# UWB-Tag_Sch.net
KiCad netlist of a schematic drawn in Altium Designer
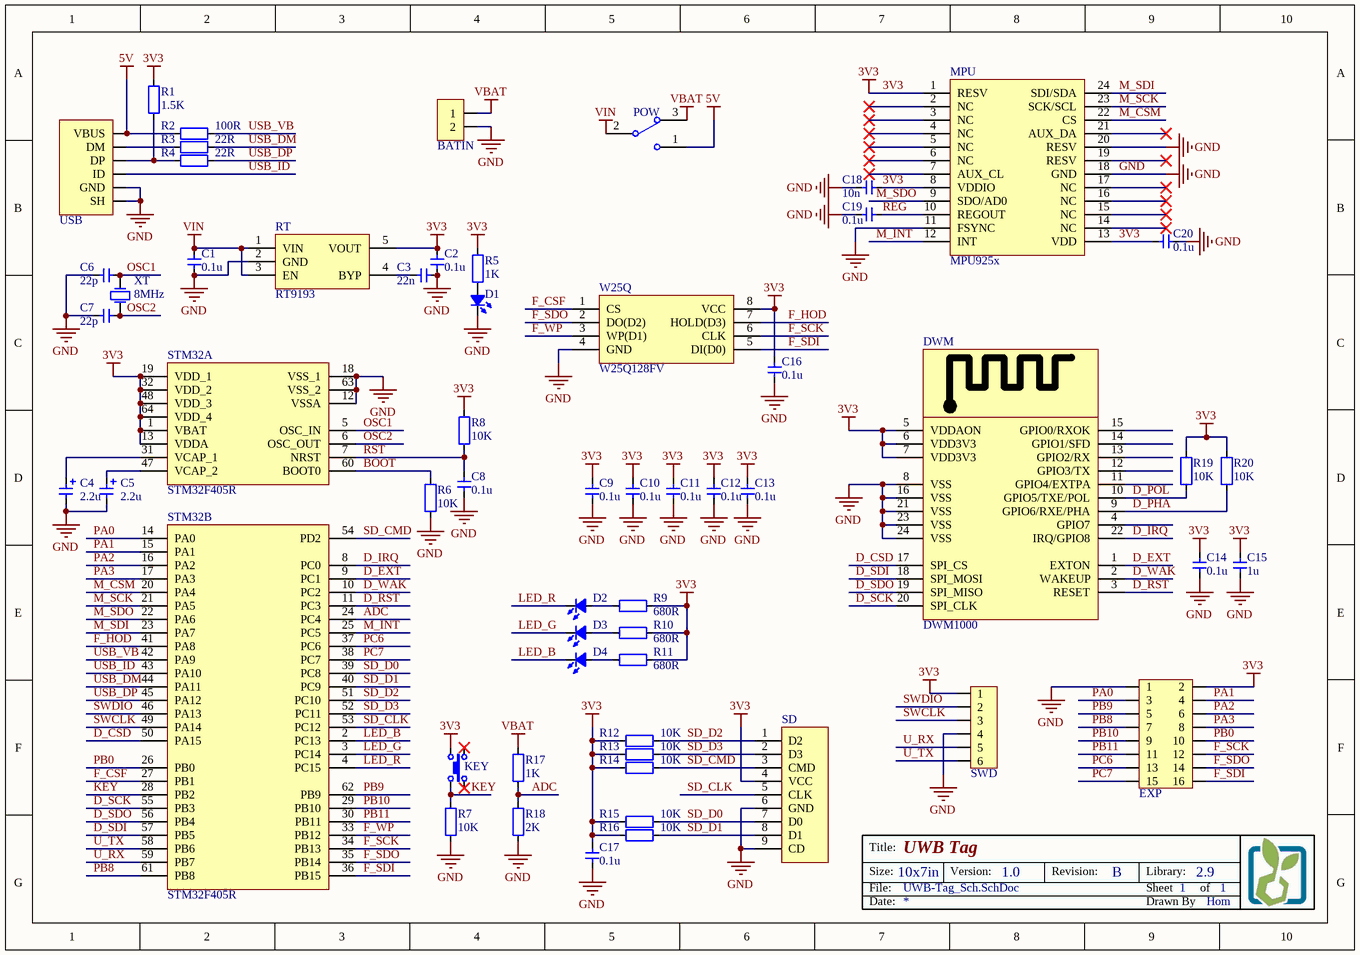
[diagram p0: UWB-Tag_Sch.SchDoc]

(export (version "E")
  (design (tool "Eeschema 10.0.6"))
  (components
    (comp (ref "BATIN")
      (value "MX1.25_2P")
      (footprint "PCB_Connector:MX1.25_S90_2P")
      (description "MX")
      (libsource (lib "SCH_Connector") (part "MX1.25_2P"))
    )
    (comp (ref "C1")
      (value "0.1u")
      (footprint "PCB_PassiveCap:CAP_0603")
      (description "Capacitor")
      (fields (field (name "Comment") "Cap_0603"))
      (libsource (lib "SCH_Passive") (part "Cap_0603"))
    )
    (comp (ref "C2")
      (value "0.1u")
      (footprint "PCB_PassiveCap:CAP_0603")
      (description "Capacitor")
      (fields (field (name "Comment") "Cap_0603"))
      (libsource (lib "SCH_Passive") (part "Cap_0603"))
    )
    (comp (ref "C3")
      (value "22n")
      (footprint "PCB_PassiveCap:CAP_0603")
      (description "Capacitor")
      (fields (field (name "Comment") "Cap_0603"))
      (libsource (lib "SCH_Passive") (part "Cap_0603"))
    )
    (comp (ref "C4")
      (value "2.2u")
      (footprint "PCB_PassiveCap:CAP_TAN_P0805")
      (description "Capacitor")
      (fields (field (name "Comment") "Cap_Tan_0805"))
      (libsource (lib "SCH_Passive") (part "Cap_Tan_0805"))
    )
    (comp (ref "C5")
      (value "2.2u")
      (footprint "PCB_PassiveCap:CAP_TAN_P0805")
      (description "Capacitor")
      (fields (field (name "Comment") "Cap_Tan_0805"))
      (libsource (lib "SCH_Passive") (part "Cap_Tan_0805"))
    )
    (comp (ref "C6")
      (value "22p")
      (footprint "PCB_PassiveCap:CAP_0603")
      (description "Capacitor")
      (fields (field (name "Comment") "Cap_0603"))
      (libsource (lib "SCH_Passive") (part "Cap_0603"))
    )
    (comp (ref "C7")
      (value "22p")
      (footprint "PCB_PassiveCap:CAP_0603")
      (description "Capacitor")
      (fields (field (name "Comment") "Cap_0603"))
      (libsource (lib "SCH_Passive") (part "Cap_0603"))
    )
    (comp (ref "C8")
      (value "0.1u")
      (footprint "PCB_PassiveCap:CAP_0603")
      (description "Capacitor")
      (fields (field (name "Comment") "Cap_0603"))
      (libsource (lib "SCH_Passive") (part "Cap_0603"))
    )
    (comp (ref "C9")
      (value "0.1u")
      (footprint "PCB_PassiveCap:CAP_0603")
      (description "Capacitor")
      (fields (field (name "Comment") "Cap_0603"))
      (libsource (lib "SCH_Passive") (part "Cap_0603"))
    )
    (comp (ref "C10")
      (value "0.1u")
      (footprint "PCB_PassiveCap:CAP_0603")
      (description "Capacitor")
      (fields (field (name "Comment") "Cap_0603"))
      (libsource (lib "SCH_Passive") (part "Cap_0603"))
    )
    (comp (ref "C11")
      (value "0.1u")
      (footprint "PCB_PassiveCap:CAP_0603")
      (description "Capacitor")
      (fields (field (name "Comment") "Cap_0603"))
      (libsource (lib "SCH_Passive") (part "Cap_0603"))
    )
    (comp (ref "C12")
      (value "0.1u")
      (footprint "PCB_PassiveCap:CAP_0603")
      (description "Capacitor")
      (fields (field (name "Comment") "Cap_0603"))
      (libsource (lib "SCH_Passive") (part "Cap_0603"))
    )
    (comp (ref "C13")
      (value "0.1u")
      (footprint "PCB_PassiveCap:CAP_0603")
      (description "Capacitor")
      (fields (field (name "Comment") "Cap_0603"))
      (libsource (lib "SCH_Passive") (part "Cap_0603"))
    )
    (comp (ref "C14")
      (value "0.1u")
      (footprint "PCB_PassiveCap:CAP_0603")
      (description "Capacitor")
      (fields (field (name "Comment") "Cap_0603"))
      (libsource (lib "SCH_Passive") (part "Cap_0603"))
    )
    (comp (ref "C15")
      (value "1u")
      (footprint "PCB_PassiveCap:CAP_0603")
      (description "Capacitor")
      (fields (field (name "Comment") "Cap_0603"))
      (libsource (lib "SCH_Passive") (part "Cap_0603"))
    )
    (comp (ref "C16")
      (value "0.1u")
      (footprint "PCB_PassiveCap:CAP_0603")
      (description "Capacitor")
      (fields (field (name "Comment") "Cap_0603"))
      (libsource (lib "SCH_Passive") (part "Cap_0603"))
    )
    (comp (ref "C17")
      (value "0.1u")
      (footprint "PCB_PassiveCap:CAP_0603")
      (description "Capacitor")
      (fields (field (name "Comment") "Cap_0603"))
      (libsource (lib "SCH_Passive") (part "Cap_0603"))
    )
    (comp (ref "C18")
      (value "10n")
      (footprint "PCB_PassiveCap:CAP_0603")
      (description "Capacitor")
      (fields (field (name "Comment") "Cap_0603"))
      (libsource (lib "SCH_Passive") (part "Cap_0603"))
    )
    (comp (ref "C19")
      (value "0.1u")
      (footprint "PCB_PassiveCap:CAP_0603")
      (description "Capacitor")
      (fields (field (name "Comment") "Cap_0603"))
      (libsource (lib "SCH_Passive") (part "Cap_0603"))
    )
    (comp (ref "C20")
      (value "0.1u")
      (footprint "PCB_PassiveCap:CAP_0603")
      (description "Capacitor")
      (fields (field (name "Comment") "Cap_0603"))
      (libsource (lib "SCH_Passive") (part "Cap_0603"))
    )
    (comp (ref "D1")
      (value "LED_0603")
      (footprint "PCB_ActiveLED:LED_0603_YELLOW")
      (description "LED")
      (libsource (lib "SCH_Active") (part "LED_0603"))
    )
    (comp (ref "D2")
      (value "LED_0603")
      (footprint "PCB_ActiveLED:LED_0603_RED")
      (description "LED")
      (libsource (lib "SCH_Active") (part "LED_0603"))
    )
    (comp (ref "D3")
      (value "LED_0603")
      (footprint "PCB_ActiveLED:LED_0603_GREEN")
      (description "LED")
      (libsource (lib "SCH_Active") (part "LED_0603"))
    )
    (comp (ref "D4")
      (value "LED_0603")
      (footprint "PCB_ActiveLED:LED_0603_BLUE")
      (description "LED")
      (libsource (lib "SCH_Active") (part "LED_0603"))
    )
    (comp (ref "DWM")
      (value "DWM1000")
      (footprint "PCB_Module:DWM1000")
      (description "Module")
      (fields (field (name "MANUFACTURER") "Decawave Limited"))
      (libsource (lib "SCH_Module") (part "DWM1000"))
    )
    (comp (ref "EXP")
      (value "HDR2x8_2.54")
      (footprint "PCB_ConnectorHDR:HDR2X8_2.54_180")
      (description "Header")
      (libsource (lib "SCH_ConnectorHDR") (part "HDR2x8_2.54"))
    )
    (comp (ref "KEY")
      (value "ButtonTACT")
      (footprint "PCB_Switch:ButtonTACT_3.5*3.55_90")
      (description "Button")
      (libsource (lib "SCH_Switch") (part "ButtonTACT"))
    )
    (comp (ref "MPU")
      (value "MPU925x")
      (footprint "PCB_IntegratedCircuit:QFN_P0.4_24")
      (description "Sensor Motion")
      (libsource (lib "SCH_IntegratedCircuit") (part "MPU925x"))
    )
    (comp (ref "POW")
      (value "SwitchSPDT_2.8x6.6_90")
      (footprint "PCB_Switch:SwitchSPDT_2.8X6.6_90")
      (description "Switch")
      (libsource (lib "SCH_Switch") (part "SwitchSPDT_2.8x6.6_90"))
    )
    (comp (ref "R1")
      (value "1.5K")
      (footprint "PCB_PassiveRes:RES_0603")
      (description "Resistor")
      (fields (field (name "Comment") "Res_0603"))
      (libsource (lib "") (part "Res_0603_2"))
    )
    (comp (ref "R2")
      (value "100R")
      (footprint "PCB_PassiveRes:RES_0603")
      (description "Resistor")
      (fields (field (name "Comment") "Res_0603"))
      (libsource (lib "SCH_Passive") (part "Res_0603"))
    )
    (comp (ref "R3")
      (value "22R")
      (footprint "PCB_PassiveRes:RES_0603")
      (description "Resistor")
      (fields (field (name "Comment") "Res_0603"))
      (libsource (lib "SCH_Passive") (part "Res_0603"))
    )
    (comp (ref "R4")
      (value "22R")
      (footprint "PCB_PassiveRes:RES_0603")
      (description "Resistor")
      (fields (field (name "Comment") "Res_0603"))
      (libsource (lib "SCH_Passive") (part "Res_0603"))
    )
    (comp (ref "R5")
      (value "1K")
      (footprint "PCB_PassiveRes:RES_0603")
      (description "Resistor")
      (fields (field (name "Comment") "Res_0603"))
      (libsource (lib "") (part "Res_0603_1"))
    )
    (comp (ref "R6")
      (value "10K")
      (footprint "PCB_PassiveRes:RES_0603")
      (description "Resistor")
      (fields (field (name "Comment") "Res_0603"))
      (libsource (lib "") (part "Res_0603_1"))
    )
    (comp (ref "R7")
      (value "10K")
      (footprint "PCB_PassiveRes:RES_0603")
      (description "Resistor")
      (fields (field (name "Comment") "Res_0603"))
      (libsource (lib "") (part "Res_0603_1"))
    )
    (comp (ref "R8")
      (value "10K")
      (footprint "PCB_PassiveRes:RES_0603")
      (description "Resistor")
      (fields (field (name "Comment") "Res_0603"))
      (libsource (lib "") (part "Res_0603_1"))
    )
    (comp (ref "R9")
      (value "680R")
      (footprint "PCB_PassiveRes:RES_0603")
      (description "Resistor")
      (fields (field (name "Comment") "Res_0603"))
      (libsource (lib "SCH_Passive") (part "Res_0603"))
    )
    (comp (ref "R10")
      (value "680R")
      (footprint "PCB_PassiveRes:RES_0603")
      (description "Resistor")
      (fields (field (name "Comment") "Res_0603"))
      (libsource (lib "SCH_Passive") (part "Res_0603"))
    )
    (comp (ref "R11")
      (value "680R")
      (footprint "PCB_PassiveRes:RES_0603")
      (description "Resistor")
      (fields (field (name "Comment") "Res_0603"))
      (libsource (lib "SCH_Passive") (part "Res_0603"))
    )
    (comp (ref "R12")
      (value "10K")
      (footprint "PCB_PassiveRes:RES_0603")
      (description "Resistor")
      (fields (field (name "Comment") "Res_0603"))
      (libsource (lib "SCH_Passive") (part "Res_0603"))
    )
    (comp (ref "R13")
      (value "10K")
      (footprint "PCB_PassiveRes:RES_0603")
      (description "Resistor")
      (fields (field (name "Comment") "Res_0603"))
      (libsource (lib "SCH_Passive") (part "Res_0603"))
    )
    (comp (ref "R14")
      (value "10K")
      (footprint "PCB_PassiveRes:RES_0603")
      (description "Resistor")
      (fields (field (name "Comment") "Res_0603"))
      (libsource (lib "SCH_Passive") (part "Res_0603"))
    )
    (comp (ref "R15")
      (value "10K")
      (footprint "PCB_PassiveRes:RES_0603")
      (description "Resistor")
      (fields (field (name "Comment") "Res_0603"))
      (libsource (lib "SCH_Passive") (part "Res_0603"))
    )
    (comp (ref "R16")
      (value "10K")
      (footprint "PCB_PassiveRes:RES_0603")
      (description "Resistor")
      (fields (field (name "Comment") "Res_0603"))
      (libsource (lib "SCH_Passive") (part "Res_0603"))
    )
    (comp (ref "R17")
      (value "1K")
      (footprint "PCB_PassiveRes:RES_0603")
      (description "Resistor")
      (fields (field (name "Comment") "Res_0603"))
      (libsource (lib "") (part "Res_0603_2"))
    )
    (comp (ref "R18")
      (value "2K")
      (footprint "PCB_PassiveRes:RES_0603")
      (description "Resistor")
      (fields (field (name "Comment") "Res_0603"))
      (libsource (lib "") (part "Res_0603_2"))
    )
    (comp (ref "R19")
      (value "10K")
      (footprint "PCB_PassiveRes:RES_0603")
      (description "Resistor")
      (fields (field (name "Comment") "Res_0603"))
      (libsource (lib "") (part "Res_0603_1"))
    )
    (comp (ref "R20")
      (value "10K")
      (footprint "PCB_PassiveRes:RES_0603")
      (description "Resistor")
      (fields (field (name "Comment") "Res_0603"))
      (libsource (lib "") (part "Res_0603_1"))
    )
    (comp (ref "RT")
      (value "RT9193")
      (footprint "PCB_IntegratedCircuit:SOT23-5")
      (description "Power")
      (libsource (lib "SCH_IntegratedCircuit") (part "RT9193"))
    )
    (comp (ref "SD")
      (value "SD_Card_TF")
      (footprint "PCB_SDCard:SD_Card_TF")
      (description "SD")
      (libsource (lib "SCH_SDCard") (part "SD_Card_TF"))
    )
    (comp (ref "STM32")
      (value "STM32F405R")
      (footprint "PCB_IntegratedCircuit:LQFP_P0.5_64")
      (description "MCU")
      (libsource (lib "SCH_IntegratedCircuit") (part "STM32F405R"))
    )
    (comp (ref "SWD")
      (value "HDR1x6_1.27")
      (footprint "PCB_ConnectorHDR:HDR1X6_1.27_180HFD")
      (description "Header")
      (libsource (lib "SCH_ConnectorHDR") (part "HDR1x6_1.27"))
    )
    (comp (ref "USB")
      (value "USB_Micro")
      (footprint "PCB_USB:USB_Micro-AB")
      (description "USB")
      (libsource (lib "SCH_USB") (part "USB_Micro"))
    )
    (comp (ref "W25Q")
      (value "W25Q128FV")
      (footprint "PCB_IntegratedCircuit:SON_P1.27H_8")
      (description "FLASH")
      (libsource (lib "SCH_IntegratedCircuit") (part "W25Q_8"))
    )
    (comp (ref "XT")
      (value "8MHz")
      (footprint "PCB_Oscillator:XT_5032_2")
      (description "Crystal Oscillator")
      (fields (field (name "Comment") "XTAL_5032_2P"))
      (libsource (lib "SCH_Oscillator") (part "XTAL_5032_2P"))
    )
  )
  (nets
    (net (code "1") (name "/ADC") (class "Default")
      (node (ref "R17") (pin "2") (pinfunction "2_2") (pintype "passive"))
      (node (ref "R18") (pin "1") (pinfunction "1_1") (pintype "passive"))
      (node (ref "STM32") (pin "24") (pinfunction "PC4_24") (pintype "passive"))
    )
    (net (code "2") (name "/BOOT") (class "Default")
      (node (ref "R6") (pin "2") (pinfunction "2_2") (pintype "passive"))
      (node (ref "STM32") (pin "60") (pinfunction "BOOT0_60") (pintype "passive"))
    )
    (net (code "3") (name "/D_CSD") (class "Default")
      (node (ref "DWM") (pin "17") (pinfunction "SPI_CS_17") (pintype "passive"))
      (node (ref "STM32") (pin "50") (pinfunction "PA15_50") (pintype "passive"))
    )
    (net (code "4") (name "/D_EXT") (class "Default")
      (node (ref "DWM") (pin "1") (pinfunction "EXTON_1") (pintype "passive"))
      (node (ref "STM32") (pin "9") (pinfunction "PC1_9") (pintype "passive"))
    )
    (net (code "5") (name "/D_IRQ") (class "Default")
      (node (ref "DWM") (pin "22") (pinfunction "IRQ/GPIO8_22") (pintype "passive"))
      (node (ref "STM32") (pin "8") (pinfunction "PC0_8") (pintype "passive"))
    )
    (net (code "6") (name "/D_PHA") (class "Default")
      (node (ref "DWM") (pin "9") (pinfunction "GPIO6/RXE/PHA_9") (pintype "passive"))
      (node (ref "R20") (pin "1") (pinfunction "1_1") (pintype "passive"))
    )
    (net (code "7") (name "/D_POL") (class "Default")
      (node (ref "DWM") (pin "10") (pinfunction "GPIO5/TXE/POL_10") (pintype "passive"))
      (node (ref "R19") (pin "1") (pinfunction "1_1") (pintype "passive"))
    )
    (net (code "8") (name "/D_RST") (class "Default")
      (node (ref "DWM") (pin "3") (pinfunction "RESET_3") (pintype "passive"))
      (node (ref "STM32") (pin "11") (pinfunction "PC3_11") (pintype "passive"))
    )
    (net (code "9") (name "/D_SCK") (class "Default")
      (node (ref "DWM") (pin "20") (pinfunction "SPI_CLK_20") (pintype "passive"))
      (node (ref "STM32") (pin "55") (pinfunction "PB3_55") (pintype "passive"))
    )
    (net (code "10") (name "/D_SDI") (class "Default")
      (node (ref "DWM") (pin "18") (pinfunction "SPI_MOSI_18") (pintype "passive"))
      (node (ref "STM32") (pin "57") (pinfunction "PB5_57") (pintype "passive"))
    )
    (net (code "11") (name "/D_SDO") (class "Default")
      (node (ref "DWM") (pin "19") (pinfunction "SPI_MISO_19") (pintype "passive"))
      (node (ref "STM32") (pin "56") (pinfunction "PB4_56") (pintype "passive"))
    )
    (net (code "12") (name "/D_WAK") (class "Default")
      (node (ref "DWM") (pin "2") (pinfunction "WAKEUP_2") (pintype "passive"))
      (node (ref "STM32") (pin "10") (pinfunction "PC2_10") (pintype "passive"))
    )
    (net (code "13") (name "/F_CSF") (class "Default")
      (node (ref "STM32") (pin "27") (pinfunction "PB1_27") (pintype "passive"))
      (node (ref "W25Q") (pin "1") (pinfunction "CS_1") (pintype "passive"))
    )
    (net (code "14") (name "/F_HOD") (class "Default")
      (node (ref "STM32") (pin "41") (pinfunction "PA8_41") (pintype "passive"))
      (node (ref "W25Q") (pin "7") (pinfunction "HOLD(D3)_7") (pintype "passive"))
    )
    (net (code "15") (name "/F_SCK") (class "Default")
      (node (ref "EXP") (pin "12") (pinfunction "12_12") (pintype "passive"))
      (node (ref "STM32") (pin "34") (pinfunction "PB13_34") (pintype "passive"))
      (node (ref "W25Q") (pin "6") (pinfunction "CLK_6") (pintype "passive"))
    )
    (net (code "16") (name "/F_SDI") (class "Default")
      (node (ref "EXP") (pin "16") (pinfunction "16_16") (pintype "passive"))
      (node (ref "STM32") (pin "36") (pinfunction "PB15_36") (pintype "passive"))
      (node (ref "W25Q") (pin "5") (pinfunction "DI(D0)_5") (pintype "passive"))
    )
    (net (code "17") (name "/F_SDO") (class "Default")
      (node (ref "EXP") (pin "14") (pinfunction "14_14") (pintype "passive"))
      (node (ref "STM32") (pin "35") (pinfunction "PB14_35") (pintype "passive"))
      (node (ref "W25Q") (pin "2") (pinfunction "DO(D2)_2") (pintype "passive"))
    )
    (net (code "18") (name "/F_WP") (class "Default")
      (node (ref "STM32") (pin "33") (pinfunction "PB12_33") (pintype "passive"))
      (node (ref "W25Q") (pin "3") (pinfunction "WP(D1)_3") (pintype "passive"))
    )
    (net (code "19") (name "/KEY") (class "Default")
      (node (ref "KEY") (pin "1") (pinfunction "1_1") (pintype "passive"))
      (node (ref "R7") (pin "2") (pinfunction "2_2") (pintype "passive"))
      (node (ref "STM32") (pin "28") (pinfunction "PB2_28") (pintype "passive"))
    )
    (net (code "20") (name "/LED_B") (class "Default")
      (node (ref "D4") (pin "2") (pinfunction "K_2") (pintype "passive"))
      (node (ref "STM32") (pin "2") (pinfunction "PC13_2") (pintype "passive"))
    )
    (net (code "21") (name "/LED_G") (class "Default")
      (node (ref "D3") (pin "2") (pinfunction "K_2") (pintype "passive"))
      (node (ref "STM32") (pin "3") (pinfunction "PC14_3") (pintype "passive"))
    )
    (net (code "22") (name "/LED_R") (class "Default")
      (node (ref "D2") (pin "2") (pinfunction "K_2") (pintype "passive"))
      (node (ref "STM32") (pin "4") (pinfunction "PC15_4") (pintype "passive"))
    )
    (net (code "23") (name "/M_CSM") (class "Default")
      (node (ref "MPU") (pin "22") (pinfunction "CS_22") (pintype "passive"))
      (node (ref "STM32") (pin "20") (pinfunction "PA4_20") (pintype "passive"))
    )
    (net (code "24") (name "/M_INT") (class "Default")
      (node (ref "MPU") (pin "12") (pinfunction "INT_12") (pintype "passive"))
      (node (ref "STM32") (pin "25") (pinfunction "PC5_25") (pintype "passive"))
    )
    (net (code "25") (name "/M_SCK") (class "Default")
      (node (ref "MPU") (pin "23") (pinfunction "SCK/SCL_23") (pintype "passive"))
      (node (ref "STM32") (pin "21") (pinfunction "PA5_21") (pintype "passive"))
    )
    (net (code "26") (name "/M_SDI") (class "Default")
      (node (ref "MPU") (pin "24") (pinfunction "SDI/SDA_24") (pintype "passive"))
      (node (ref "STM32") (pin "23") (pinfunction "PA7_23") (pintype "passive"))
    )
    (net (code "27") (name "/M_SDO") (class "Default")
      (node (ref "MPU") (pin "9") (pinfunction "SDO/AD0_9") (pintype "passive"))
      (node (ref "STM32") (pin "22") (pinfunction "PA6_22") (pintype "passive"))
    )
    (net (code "28") (name "/OSC1") (class "Default")
      (node (ref "C6") (pin "1") (pinfunction "1_1") (pintype "passive"))
      (node (ref "STM32") (pin "5") (pinfunction "OSC_IN_5") (pintype "passive"))
      (node (ref "XT") (pin "2") (pinfunction "OSC2_2") (pintype "passive"))
    )
    (net (code "29") (name "/OSC2") (class "Default")
      (node (ref "C7") (pin "1") (pinfunction "1_1") (pintype "passive"))
      (node (ref "STM32") (pin "6") (pinfunction "OSC_OUT_6") (pintype "passive"))
      (node (ref "XT") (pin "1") (pinfunction "OSC1_1") (pintype "passive"))
    )
    (net (code "30") (name "/PA0") (class "Default")
      (node (ref "EXP") (pin "3") (pinfunction "3_3") (pintype "passive"))
      (node (ref "STM32") (pin "14") (pinfunction "PA0_14") (pintype "passive"))
    )
    (net (code "31") (name "/PA1") (class "Default")
      (node (ref "EXP") (pin "4") (pinfunction "4_4") (pintype "passive"))
      (node (ref "STM32") (pin "15") (pinfunction "PA1_15") (pintype "passive"))
    )
    (net (code "32") (name "/PA2") (class "Default")
      (node (ref "EXP") (pin "6") (pinfunction "6_6") (pintype "passive"))
      (node (ref "STM32") (pin "16") (pinfunction "PA2_16") (pintype "passive"))
    )
    (net (code "33") (name "/PA3") (class "Default")
      (node (ref "EXP") (pin "8") (pinfunction "8_8") (pintype "passive"))
      (node (ref "STM32") (pin "17") (pinfunction "PA3_17") (pintype "passive"))
    )
    (net (code "34") (name "/PB0") (class "Default")
      (node (ref "EXP") (pin "10") (pinfunction "10_10") (pintype "passive"))
      (node (ref "STM32") (pin "26") (pinfunction "PB0_26") (pintype "passive"))
    )
    (net (code "35") (name "/PB8") (class "Default")
      (node (ref "EXP") (pin "7") (pinfunction "7_7") (pintype "passive"))
      (node (ref "STM32") (pin "61") (pinfunction "PB8_61") (pintype "passive"))
    )
    (net (code "36") (name "/PB9") (class "Default")
      (node (ref "EXP") (pin "5") (pinfunction "5_5") (pintype "passive"))
      (node (ref "STM32") (pin "62") (pinfunction "PB9_62") (pintype "passive"))
    )
    (net (code "37") (name "/PB10") (class "Default")
      (node (ref "EXP") (pin "9") (pinfunction "9_9") (pintype "passive"))
      (node (ref "STM32") (pin "29") (pinfunction "PB10_29") (pintype "passive"))
    )
    (net (code "38") (name "/PB11") (class "Default")
      (node (ref "EXP") (pin "11") (pinfunction "11_11") (pintype "passive"))
      (node (ref "STM32") (pin "30") (pinfunction "PB11_30") (pintype "passive"))
    )
    (net (code "39") (name "/PC6") (class "Default")
      (node (ref "EXP") (pin "13") (pinfunction "13_13") (pintype "passive"))
      (node (ref "STM32") (pin "37") (pinfunction "PC6_37") (pintype "passive"))
    )
    (net (code "40") (name "/PC7") (class "Default")
      (node (ref "EXP") (pin "15") (pinfunction "15_15") (pintype "passive"))
      (node (ref "STM32") (pin "38") (pinfunction "PC7_38") (pintype "passive"))
    )
    (net (code "41") (name "/REG") (class "Default")
      (node (ref "C19") (pin "2") (pinfunction "2_2") (pintype "passive"))
      (node (ref "MPU") (pin "10") (pinfunction "REGOUT_10") (pintype "passive"))
    )
    (net (code "42") (name "/RST") (class "Default")
      (node (ref "C8") (pin "2") (pinfunction "2_2") (pintype "passive"))
      (node (ref "R8") (pin "1") (pinfunction "1_1") (pintype "passive"))
      (node (ref "STM32") (pin "7") (pinfunction "NRST_7") (pintype "passive"))
    )
    (net (code "43") (name "/SD_CLK") (class "Default")
      (node (ref "SD") (pin "5") (pinfunction "CLK_5") (pintype "passive"))
      (node (ref "STM32") (pin "53") (pinfunction "PC12_53") (pintype "passive"))
    )
    (net (code "44") (name "/SD_CMD") (class "Default")
      (node (ref "R14") (pin "1") (pinfunction "1_1") (pintype "passive"))
      (node (ref "SD") (pin "3") (pinfunction "CMD_3") (pintype "passive"))
      (node (ref "STM32") (pin "54") (pinfunction "PD2_54") (pintype "passive"))
    )
    (net (code "45") (name "/SD_D0") (class "Default")
      (node (ref "R15") (pin "1") (pinfunction "1_1") (pintype "passive"))
      (node (ref "SD") (pin "7") (pinfunction "D0_7") (pintype "passive"))
      (node (ref "STM32") (pin "39") (pinfunction "PC8_39") (pintype "passive"))
    )
    (net (code "46") (name "/SD_D1") (class "Default")
      (node (ref "R16") (pin "1") (pinfunction "1_1") (pintype "passive"))
      (node (ref "SD") (pin "8") (pinfunction "D1_8") (pintype "passive"))
      (node (ref "STM32") (pin "40") (pinfunction "PC9_40") (pintype "passive"))
    )
    (net (code "47") (name "/SD_D2") (class "Default")
      (node (ref "R12") (pin "1") (pinfunction "1_1") (pintype "passive"))
      (node (ref "SD") (pin "1") (pinfunction "D2_1") (pintype "passive"))
      (node (ref "STM32") (pin "51") (pinfunction "PC10_51") (pintype "passive"))
    )
    (net (code "48") (name "/SD_D3") (class "Default")
      (node (ref "R13") (pin "1") (pinfunction "1_1") (pintype "passive"))
      (node (ref "SD") (pin "2") (pinfunction "D3_2") (pintype "passive"))
      (node (ref "STM32") (pin "52") (pinfunction "PC11_52") (pintype "passive"))
    )
    (net (code "49") (name "/SWCLK") (class "Default")
      (node (ref "STM32") (pin "49") (pinfunction "PA14_49") (pintype "passive"))
      (node (ref "SWD") (pin "3") (pinfunction "3_3") (pintype "passive"))
    )
    (net (code "50") (name "/SWDIO") (class "Default")
      (node (ref "STM32") (pin "46") (pinfunction "PA13_46") (pintype "passive"))
      (node (ref "SWD") (pin "2") (pinfunction "2_2") (pintype "passive"))
    )
    (net (code "51") (name "/USB_DM") (class "Default")
      (node (ref "R3") (pin "1") (pinfunction "1_1") (pintype "passive"))
      (node (ref "STM32") (pin "44") (pinfunction "PA11_44") (pintype "passive"))
    )
    (net (code "52") (name "/USB_DP") (class "Default")
      (node (ref "R4") (pin "1") (pinfunction "1_1") (pintype "passive"))
      (node (ref "STM32") (pin "45") (pinfunction "PA12_45") (pintype "passive"))
    )
    (net (code "53") (name "/USB_ID") (class "Default")
      (node (ref "STM32") (pin "43") (pinfunction "PA10_43") (pintype "passive"))
      (node (ref "USB") (pin "4") (pinfunction "ID_4") (pintype "passive"))
    )
    (net (code "54") (name "/USB_VB") (class "Default")
      (node (ref "R2") (pin "1") (pinfunction "1_1") (pintype "passive"))
      (node (ref "STM32") (pin "42") (pinfunction "PA9_42") (pintype "passive"))
    )
    (net (code "55") (name "/U_RX") (class "Default")
      (node (ref "STM32") (pin "59") (pinfunction "PB7_59") (pintype "passive"))
      (node (ref "SWD") (pin "5") (pinfunction "5_5") (pintype "passive"))
    )
    (net (code "56") (name "/U_TX") (class "Default")
      (node (ref "STM32") (pin "58") (pinfunction "PB6_58") (pintype "passive"))
      (node (ref "SWD") (pin "6") (pinfunction "6_6") (pintype "passive"))
    )
    (net (code "57") (name "3V3") (class "Default")
      (node (ref "C10") (pin "1") (pinfunction "1_1") (pintype "passive"))
      (node (ref "C11") (pin "1") (pinfunction "1_1") (pintype "passive"))
      (node (ref "C12") (pin "1") (pinfunction "1_1") (pintype "passive"))
      (node (ref "C13") (pin "2") (pinfunction "2_2") (pintype "passive"))
      (node (ref "C14") (pin "1") (pinfunction "1_1") (pintype "passive"))
      (node (ref "C15") (pin "1") (pinfunction "1_1") (pintype "passive"))
      (node (ref "C16") (pin "1") (pinfunction "1_1") (pintype "passive"))
      (node (ref "C17") (pin "1") (pinfunction "1_1") (pintype "passive"))
      (node (ref "C18") (pin "2") (pinfunction "2_2") (pintype "passive"))
      (node (ref "C2") (pin "2") (pinfunction "2_2") (pintype "passive"))
      (node (ref "C20") (pin "2") (pinfunction "2_2") (pintype "passive"))
      (node (ref "C9") (pin "1") (pinfunction "1_1") (pintype "passive"))
      (node (ref "DWM") (pin "5") (pinfunction "VDDAON_5") (pintype "passive"))
      (node (ref "DWM") (pin "6") (pinfunction "VDD3V3_6") (pintype "passive"))
      (node (ref "DWM") (pin "7") (pinfunction "VDD3V3_7") (pintype "passive"))
      (node (ref "EXP") (pin "2") (pinfunction "2_2") (pintype "passive"))
      (node (ref "KEY") (pin "2") (pinfunction "2_2") (pintype "passive"))
      (node (ref "MPU") (pin "1") (pinfunction "RESV_1") (pintype "passive"))
      (node (ref "MPU") (pin "13") (pinfunction "VDD_13") (pintype "passive"))
      (node (ref "MPU") (pin "8") (pinfunction "VDDIO_8") (pintype "passive"))
      (node (ref "R1") (pin "1") (pinfunction "1_1") (pintype "passive"))
      (node (ref "R10") (pin "1") (pinfunction "1_1") (pintype "passive"))
      (node (ref "R11") (pin "1") (pinfunction "1_1") (pintype "passive"))
      (node (ref "R12") (pin "2") (pinfunction "2_2") (pintype "passive"))
      (node (ref "R13") (pin "2") (pinfunction "2_2") (pintype "passive"))
      (node (ref "R14") (pin "2") (pinfunction "2_2") (pintype "passive"))
      (node (ref "R15") (pin "2") (pinfunction "2_2") (pintype "passive"))
      (node (ref "R16") (pin "2") (pinfunction "2_2") (pintype "passive"))
      (node (ref "R19") (pin "2") (pinfunction "2_2") (pintype "passive"))
      (node (ref "R20") (pin "2") (pinfunction "2_2") (pintype "passive"))
      (node (ref "R5") (pin "2") (pinfunction "2_2") (pintype "passive"))
      (node (ref "R8") (pin "2") (pinfunction "2_2") (pintype "passive"))
      (node (ref "R9") (pin "1") (pinfunction "1_1") (pintype "passive"))
      (node (ref "RT") (pin "5") (pinfunction "VOUT_5") (pintype "passive"))
      (node (ref "SD") (pin "4") (pinfunction "VCC_4") (pintype "passive"))
      (node (ref "STM32") (pin "1") (pinfunction "VBAT_1") (pintype "passive"))
      (node (ref "STM32") (pin "13") (pinfunction "VDDA_13") (pintype "passive"))
      (node (ref "STM32") (pin "19") (pinfunction "VDD_1_19") (pintype "passive"))
      (node (ref "STM32") (pin "32") (pinfunction "VDD_2_32") (pintype "passive"))
      (node (ref "STM32") (pin "48") (pinfunction "VDD_3_48") (pintype "passive"))
      (node (ref "STM32") (pin "64") (pinfunction "VDD_4_64") (pintype "passive"))
      (node (ref "SWD") (pin "1") (pinfunction "1_1") (pintype "passive"))
      (node (ref "W25Q") (pin "8") (pinfunction "VCC_8") (pintype "passive"))
    )
    (net (code "58") (name "5V") (class "Default")
      (node (ref "POW") (pin "1") (pinfunction "1_1") (pintype "passive"))
      (node (ref "R2") (pin "2") (pinfunction "2_2") (pintype "passive"))
      (node (ref "USB") (pin "1") (pinfunction "VBUS_1") (pintype "passive"))
    )
    (net (code "59") (name "GND") (class "Default")
      (node (ref "BATIN") (pin "2") (pinfunction "2_2") (pintype "passive"))
      (node (ref "C1") (pin "1") (pinfunction "1_1") (pintype "passive"))
      (node (ref "C10") (pin "2") (pinfunction "2_2") (pintype "passive"))
      (node (ref "C11") (pin "2") (pinfunction "2_2") (pintype "passive"))
      (node (ref "C12") (pin "2") (pinfunction "2_2") (pintype "passive"))
      (node (ref "C13") (pin "1") (pinfunction "1_1") (pintype "passive"))
      (node (ref "C14") (pin "2") (pinfunction "2_2") (pintype "passive"))
      (node (ref "C15") (pin "2") (pinfunction "2_2") (pintype "passive"))
      (node (ref "C16") (pin "2") (pinfunction "2_2") (pintype "passive"))
      (node (ref "C17") (pin "2") (pinfunction "2_2") (pintype "passive"))
      (node (ref "C18") (pin "1") (pinfunction "1_1") (pintype "passive"))
      (node (ref "C19") (pin "1") (pinfunction "1_1") (pintype "passive"))
      (node (ref "C2") (pin "1") (pinfunction "1_1") (pintype "passive"))
      (node (ref "C20") (pin "1") (pinfunction "1_1") (pintype "passive"))
      (node (ref "C3") (pin "1") (pinfunction "1_1") (pintype "passive"))
      (node (ref "C4") (pin "2") (pinfunction "2_2") (pintype "passive"))
      (node (ref "C5") (pin "2") (pinfunction "2_2") (pintype "passive"))
      (node (ref "C6") (pin "2") (pinfunction "2_2") (pintype "passive"))
      (node (ref "C7") (pin "2") (pinfunction "2_2") (pintype "passive"))
      (node (ref "C8") (pin "1") (pinfunction "1_1") (pintype "passive"))
      (node (ref "C9") (pin "2") (pinfunction "2_2") (pintype "passive"))
      (node (ref "D1") (pin "2") (pinfunction "K_2") (pintype "passive"))
      (node (ref "DWM") (pin "16") (pinfunction "VSS_16") (pintype "passive"))
      (node (ref "DWM") (pin "21") (pinfunction "VSS_21") (pintype "passive"))
      (node (ref "DWM") (pin "23") (pinfunction "VSS_23") (pintype "passive"))
      (node (ref "DWM") (pin "24") (pinfunction "VSS_24") (pintype "passive"))
      (node (ref "DWM") (pin "8") (pinfunction "VSS_8") (pintype "passive"))
      (node (ref "EXP") (pin "1") (pinfunction "1_1") (pintype "passive"))
      (node (ref "MPU") (pin "11") (pinfunction "FSYNC_11") (pintype "passive"))
      (node (ref "MPU") (pin "18") (pinfunction "GND_18") (pintype "passive"))
      (node (ref "MPU") (pin "20") (pinfunction "RESV_20") (pintype "passive"))
      (node (ref "R18") (pin "2") (pinfunction "2_2") (pintype "passive"))
      (node (ref "R6") (pin "1") (pinfunction "1_1") (pintype "passive"))
      (node (ref "R7") (pin "1") (pinfunction "1_1") (pintype "passive"))
      (node (ref "RT") (pin "2") (pinfunction "GND_2") (pintype "passive"))
      (node (ref "SD") (pin "6") (pinfunction "GND_6") (pintype "passive"))
      (node (ref "SD") (pin "9") (pinfunction "CD_9") (pintype "passive"))
      (node (ref "STM32") (pin "12") (pinfunction "VSSA_12") (pintype "passive"))
      (node (ref "STM32") (pin "18") (pinfunction "VSS_1_18") (pintype "passive"))
      (node (ref "STM32") (pin "63") (pinfunction "VSS_2_63") (pintype "passive"))
      (node (ref "SWD") (pin "4") (pinfunction "4_4") (pintype "passive"))
      (node (ref "USB") (pin "0") (pinfunction "SH_0") (pintype "passive"))
      (node (ref "USB") (pin "5") (pinfunction "GND_5") (pintype "passive"))
      (node (ref "W25Q") (pin "4") (pinfunction "GND_4") (pintype "passive"))
    )
    (net (code "60") (name "Net-(D1-A)") (class "Default")
      (node (ref "D1") (pin "1") (pinfunction "A_1") (pintype "passive"))
      (node (ref "R5") (pin "1") (pinfunction "1_1") (pintype "passive"))
    )
    (net (code "61") (name "Net-(D2-A)") (class "Default")
      (node (ref "D2") (pin "1") (pinfunction "A_1") (pintype "passive"))
      (node (ref "R9") (pin "2") (pinfunction "2_2") (pintype "passive"))
    )
    (net (code "62") (name "Net-(D3-A)") (class "Default")
      (node (ref "D3") (pin "1") (pinfunction "A_1") (pintype "passive"))
      (node (ref "R10") (pin "2") (pinfunction "2_2") (pintype "passive"))
    )
    (net (code "63") (name "Net-(D4-A)") (class "Default")
      (node (ref "D4") (pin "1") (pinfunction "A_1") (pintype "passive"))
      (node (ref "R11") (pin "2") (pinfunction "2_2") (pintype "passive"))
    )
    (net (code "64") (name "Net-(RT-BYP)") (class "Default")
      (node (ref "C3") (pin "2") (pinfunction "2_2") (pintype "passive"))
      (node (ref "RT") (pin "4") (pinfunction "BYP_4") (pintype "passive"))
    )
    (net (code "65") (name "Net-(STM32A-VCAP_1)") (class "Default")
      (node (ref "C4") (pin "1") (pinfunction "1_1") (pintype "passive"))
      (node (ref "STM32") (pin "31") (pinfunction "VCAP_1_31") (pintype "passive"))
    )
    (net (code "66") (name "Net-(STM32A-VCAP_2)") (class "Default")
      (node (ref "C5") (pin "1") (pinfunction "1_1") (pintype "passive"))
      (node (ref "STM32") (pin "47") (pinfunction "VCAP_2_47") (pintype "passive"))
    )
    (net (code "67") (name "Net-(USB-DM)") (class "Default")
      (node (ref "R3") (pin "2") (pinfunction "2_2") (pintype "passive"))
      (node (ref "USB") (pin "2") (pinfunction "DM_2") (pintype "passive"))
    )
    (net (code "68") (name "Net-(USB-DP)") (class "Default")
      (node (ref "R1") (pin "2") (pinfunction "2_2") (pintype "passive"))
      (node (ref "R4") (pin "2") (pinfunction "2_2") (pintype "passive"))
      (node (ref "USB") (pin "3") (pinfunction "DP_3") (pintype "passive"))
    )
    (net (code "69") (name "VBAT") (class "Default")
      (node (ref "BATIN") (pin "1") (pinfunction "1_1") (pintype "passive"))
      (node (ref "POW") (pin "3") (pinfunction "3_3") (pintype "passive"))
      (node (ref "R17") (pin "1") (pinfunction "1_1") (pintype "passive"))
    )
    (net (code "70") (name "VIN") (class "Default")
      (node (ref "C1") (pin "2") (pinfunction "2_2") (pintype "passive"))
      (node (ref "POW") (pin "2") (pinfunction "2_2") (pintype "passive"))
      (node (ref "RT") (pin "1") (pinfunction "VIN_1") (pintype "passive"))
      (node (ref "RT") (pin "3") (pinfunction "EN_3") (pintype "power_in"))
    )
    (net (code "71") (name "unconnected-(DWM-GPIO0{slash}RXOK-Pad15)") (class "Default")
      (node (ref "DWM") (pin "15") (pinfunction "GPIO0/RXOK_15") (pintype "passive"))
    )
    (net (code "72") (name "unconnected-(DWM-GPIO1{slash}SFD-Pad14)") (class "Default")
      (node (ref "DWM") (pin "14") (pinfunction "GPIO1/SFD_14") (pintype "passive"))
    )
    (net (code "73") (name "unconnected-(DWM-GPIO2{slash}RX-Pad13)") (class "Default")
      (node (ref "DWM") (pin "13") (pinfunction "GPIO2/RX_13") (pintype "passive"))
    )
    (net (code "74") (name "unconnected-(DWM-GPIO3{slash}TX-Pad12)") (class "Default")
      (node (ref "DWM") (pin "12") (pinfunction "GPIO3/TX_12") (pintype "passive"))
    )
    (net (code "75") (name "unconnected-(DWM-GPIO4{slash}EXTPA-Pad11)") (class "Default")
      (node (ref "DWM") (pin "11") (pinfunction "GPIO4/EXTPA_11") (pintype "passive"))
    )
    (net (code "76") (name "unconnected-(DWM-GPIO7-Pad4)") (class "Default")
      (node (ref "DWM") (pin "4") (pinfunction "GPIO7_4") (pintype "passive"))
    )
    (net (code "77") (name "unconnected-(KEY-Pad3)") (class "Default")
      (node (ref "KEY") (pin "3") (pinfunction "3_3") (pintype "passive+no_connect"))
    )
    (net (code "78") (name "unconnected-(KEY-Pad4)") (class "Default")
      (node (ref "KEY") (pin "4") (pinfunction "4_4") (pintype "passive+no_connect"))
    )
    (net (code "79") (name "unconnected-(MPU-AUX_CL-Pad7)") (class "Default")
      (node (ref "MPU") (pin "7") (pinfunction "AUX_CL_7") (pintype "passive+no_connect"))
    )
    (net (code "80") (name "unconnected-(MPU-AUX_DA-Pad21)") (class "Default")
      (node (ref "MPU") (pin "21") (pinfunction "AUX_DA_21") (pintype "passive+no_connect"))
    )
    (net (code "81") (name "unconnected-(MPU-NC-Pad2)") (class "Default")
      (node (ref "MPU") (pin "2") (pinfunction "NC_2") (pintype "passive+no_connect"))
    )
    (net (code "82") (name "unconnected-(MPU-NC-Pad3)") (class "Default")
      (node (ref "MPU") (pin "3") (pinfunction "NC_3") (pintype "passive+no_connect"))
    )
    (net (code "83") (name "unconnected-(MPU-NC-Pad4)") (class "Default")
      (node (ref "MPU") (pin "4") (pinfunction "NC_4") (pintype "passive+no_connect"))
    )
    (net (code "84") (name "unconnected-(MPU-NC-Pad5)") (class "Default")
      (node (ref "MPU") (pin "5") (pinfunction "NC_5") (pintype "passive+no_connect"))
    )
    (net (code "85") (name "unconnected-(MPU-NC-Pad6)") (class "Default")
      (node (ref "MPU") (pin "6") (pinfunction "NC_6") (pintype "passive+no_connect"))
    )
    (net (code "86") (name "unconnected-(MPU-NC-Pad14)") (class "Default")
      (node (ref "MPU") (pin "14") (pinfunction "NC_14") (pintype "passive+no_connect"))
    )
    (net (code "87") (name "unconnected-(MPU-NC-Pad15)") (class "Default")
      (node (ref "MPU") (pin "15") (pinfunction "NC_15") (pintype "passive+no_connect"))
    )
    (net (code "88") (name "unconnected-(MPU-NC-Pad16)") (class "Default")
      (node (ref "MPU") (pin "16") (pinfunction "NC_16") (pintype "passive+no_connect"))
    )
    (net (code "89") (name "unconnected-(MPU-NC-Pad17)") (class "Default")
      (node (ref "MPU") (pin "17") (pinfunction "NC_17") (pintype "passive+no_connect"))
    )
    (net (code "90") (name "unconnected-(MPU-RESV-Pad19)") (class "Default")
      (node (ref "MPU") (pin "19") (pinfunction "RESV_19") (pintype "passive+no_connect"))
    )
  )
)
